# USBIface.net
KiCad netlist of a schematic drawn in Altium Designer
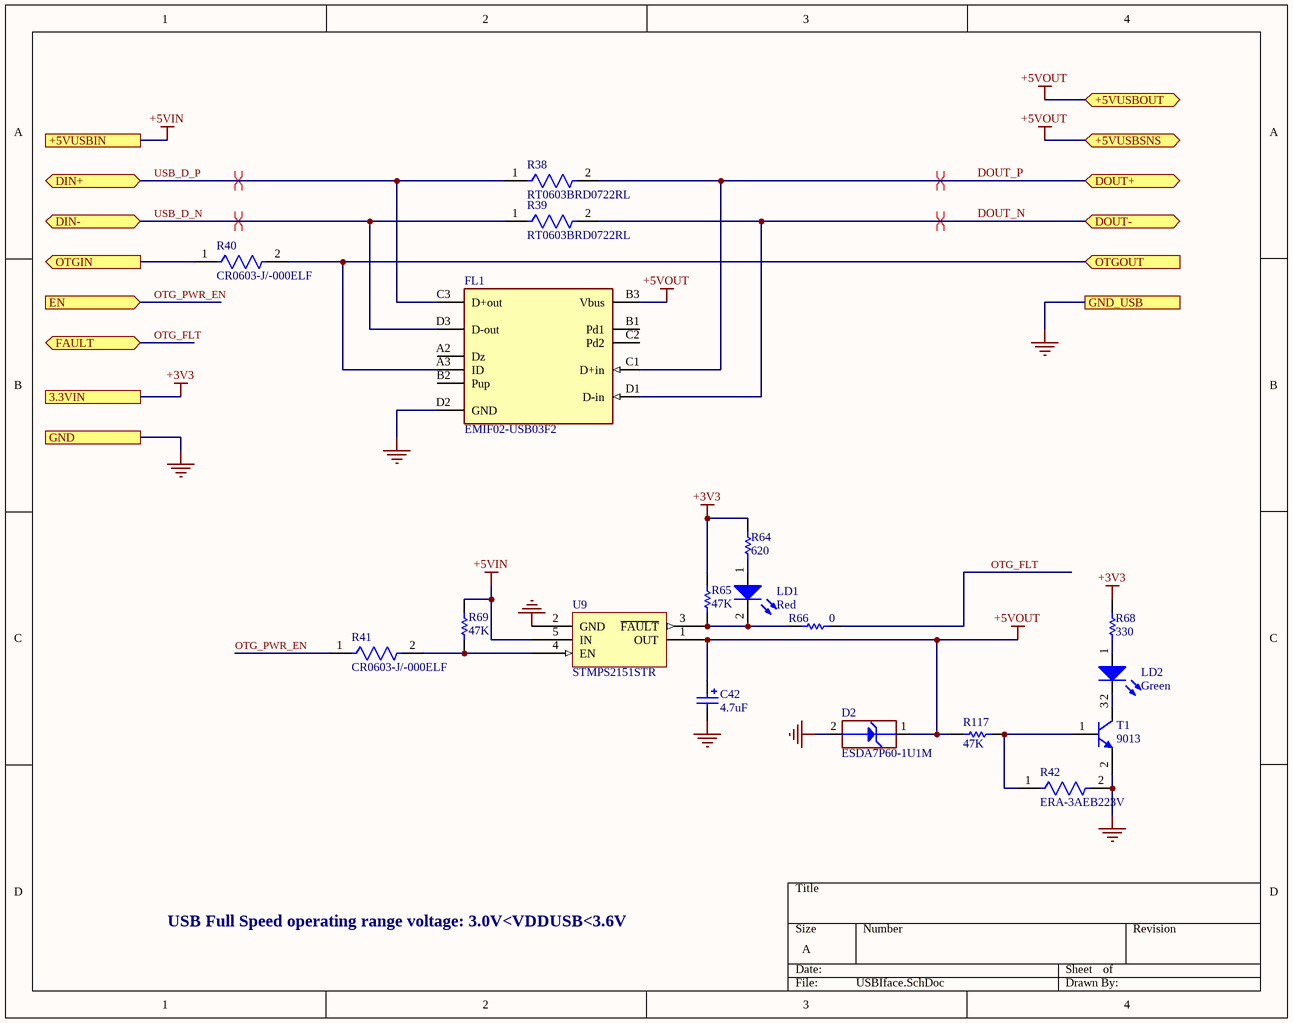
[diagram p0: USBIface.SchDoc]

(export (version "E")
  (design (tool "Eeschema 10.0.6"))
  (components
    (comp (ref "C42")
      (value "4.7uF")
      (footprint "TAN-A")
      (description "Polarized Capacitor (Radial)")
      (fields (field (name "PUBLISHER") "Altium Limited"))
      (libsource (lib "Miscellaneous Devices") (part "Cap Pol1"))
    )
    (comp (ref "D2")
      (value "ESDA7P60-1U1M")
      (footprint "DO_2SM_1R6X1_21")
      (description "High power transient voltage suppressor, 7V breakdown")
      (fields (field (name "INTERNAL_PART_NUMBER") "MCD-00251") (field (name "PROVIDED_BY") "STM"))
      (libsource (lib "MCD_PARTS_database") (part "ESDA7P60-1U1M"))
    )
    (comp (ref "FL1")
      (value "EMIF02-USB03F2")
      (footprint "FP-EMIF02-USB03F2-MFG")
      (description "FILTER RC(PI) 33 OHM/20PF SMD")
      (fields (field (name "TOLERANCE") "5%"))
      (libsource (lib "Altium Content Vault") (part "91055883b371ba38c36932eb47b762f"))
    )
    (comp (ref "LD1")
      (value "Red")
      (footprint "0603D")
      (description "Typical RED, GREEN, YELLOW, AMBER GaAs LED")
      (fields (field (name "PUBLISHER") "Altium Limited"))
      (libsource (lib "Miscellaneous Devices") (part "LED2"))
    )
    (comp (ref "LD2")
      (value "Green")
      (footprint "0603D")
      (description "Typical RED, GREEN, YELLOW, AMBER GaAs LED")
      (fields (field (name "PUBLISHER") "Altium Limited"))
      (libsource (lib "Miscellaneous Devices") (part "LED2"))
    )
    (comp (ref "R38")
      (value "RT0603BRD0722RL")
      (footprint "FP-RT0603-MFG")
      (description "RES SMD 22 OHM 0.1% 1/10W 0603")
      (fields
        (field (name "MANUFACTURER") "Yageo")
        (field (name "OCTOPART") "https://octopart.com/rt0603brd0722rl-yageo-1422899")
      )
      (libsource (lib "Altium Content Vault") (part "1029c3af85768c4190bb7ad29bc67b5"))
    )
    (comp (ref "R39")
      (value "RT0603BRD0722RL")
      (footprint "FP-RT0603-MFG")
      (description "RES SMD 22 OHM 0.1% 1/10W 0603")
      (fields
        (field (name "MANUFACTURER") "Yageo")
        (field (name "OCTOPART") "https://octopart.com/rt0603brd0722rl-yageo-1422899")
      )
      (libsource (lib "Altium Content Vault") (part "1029c3af85768c4190bb7ad29bc67b5"))
    )
    (comp (ref "R40")
      (value "CR0603-J/-000ELF")
      (footprint "FP-CR0603-MFG")
      (description "Thick Film Chip Resistors 0603 0Ω 0.1W 5%")
      (fields (field (name "TOLERANCE") "1%"))
      (libsource (lib "Altium Content Vault") (part "1029c3af85768c4190bb7ad29bc67b5"))
    )
    (comp (ref "R41")
      (value "CR0603-J/-000ELF")
      (footprint "FP-CR0603-MFG")
      (description "Thick Film Chip Resistors 0603 0Ω 0.1W 5%")
      (fields (field (name "TOLERANCE") "1%"))
      (libsource (lib "Altium Content Vault") (part "1029c3af85768c4190bb7ad29bc67b5"))
    )
    (comp (ref "R42")
      (value "ERA-3AEB223V")
      (footprint "FP-ERA3A-MFG")
      (description "RES SMD 22K OHM 0.1% 1/10W 0603")
      (fields (field (name "TOLERANCE") "0.1%"))
      (libsource (lib "Altium Content Vault") (part "1029c3af85768c4190bb7ad29bc67b5"))
    )
    (comp (ref "R64")
      (value "620")
      (footprint "0603R")
      (description "Resistor")
      (fields (field (name "PUBLISHER") "Altium Limited"))
      (libsource (lib "Miscellaneous Devices") (part "Res1"))
    )
    (comp (ref "R65")
      (value "47K")
      (footprint "0603R")
      (description "Resistor")
      (fields (field (name "PUBLISHER") "Altium Limited"))
      (libsource (lib "Miscellaneous Devices") (part "res1"))
    )
    (comp (ref "R66")
      (value "0")
      (footprint "0603R")
      (description "Resistor")
      (fields (field (name "PUBLISHER") "Altium Limited"))
      (libsource (lib "Miscellaneous Devices") (part "Res1"))
    )
    (comp (ref "R68")
      (value "330")
      (footprint "0603R")
      (description "Resistor")
      (fields (field (name "PUBLISHER") "Altium Limited"))
      (libsource (lib "Miscellaneous Devices") (part "res1"))
    )
    (comp (ref "R69")
      (value "47K")
      (footprint "0603R")
      (description "Resistor")
      (fields (field (name "PUBLISHER") "Altium Limited"))
      (libsource (lib "Miscellaneous Devices") (part "Res1"))
    )
    (comp (ref "R117")
      (value "47K")
      (footprint "0603R")
      (description "Resistor")
      (fields (field (name "PUBLISHER") "Altium Limited"))
      (libsource (lib "Miscellaneous Devices") (part "res1"))
    )
    (comp (ref "T1")
      (value "9013")
      (footprint "SOT-23")
      (description "NPN Bipolar Transistor")
      (fields (field (name "PUBLISHER") "Altium Limited"))
      (libsource (lib "MB1167") (part "NPN"))
    )
    (comp (ref "U9")
      (value "STMPS2151STR")
      (footprint "SOT23-5N")
      (libsource (lib "mb1045") (part "STMPS2141STR"))
    )
  )
  (nets
    (net (code "1") (name "+3V3") (class "Default")
      (node (ref "R64") (pin "2") (pinfunction "2_2") (pintype "passive"))
      (node (ref "R65") (pin "1") (pinfunction "1_1") (pintype "passive"))
      (node (ref "R68") (pin "2") (pinfunction "2_2") (pintype "passive"))
    )
    (net (code "2") (name "+5VIN") (class "Default")
      (node (ref "R69") (pin "2") (pinfunction "2_2") (pintype "passive"))
      (node (ref "U9") (pin "5") (pinfunction "IN_5") (pintype "passive"))
    )
    (net (code "3") (name "+5VOUT") (class "Default")
      (node (ref "C42") (pin "1") (pinfunction "1_1") (pintype "passive"))
      (node (ref "D2") (pin "1") (pinfunction "IO1_1") (pintype "passive"))
      (node (ref "FL1") (pin "B3") (pinfunction "Vbus_B3") (pintype "passive"))
      (node (ref "R117") (pin "1") (pinfunction "1_1") (pintype "passive"))
      (node (ref "U9") (pin "1") (pinfunction "OUT_1") (pintype "passive"))
    )
    (net (code "4") (name "/DOUT_N") (class "Default")
      (node (ref "FL1") (pin "D1") (pinfunction "D-in_D1") (pintype "input"))
      (node (ref "R39") (pin "2") (pinfunction "2_2") (pintype "passive"))
    )
    (net (code "5") (name "/DOUT_P") (class "Default")
      (node (ref "FL1") (pin "C1") (pinfunction "D+in_C1") (pintype "input"))
      (node (ref "R38") (pin "2") (pinfunction "2_2") (pintype "passive"))
    )
    (net (code "6") (name "/OTGIN") (class "Default")
      (node (ref "R40") (pin "1") (pinfunction "1_1") (pintype "passive"))
    )
    (net (code "7") (name "/OTGOUT") (class "Default")
      (node (ref "FL1") (pin "A3") (pinfunction "ID_A3") (pintype "passive"))
      (node (ref "R40") (pin "2") (pinfunction "2_2") (pintype "passive"))
    )
    (net (code "8") (name "/OTG_FLT") (class "Default")
      (node (ref "R66") (pin "1") (pinfunction "1_1") (pintype "passive"))
    )
    (net (code "9") (name "/OTG_PWR_EN") (class "Default")
      (node (ref "R41") (pin "1") (pinfunction "1_1") (pintype "passive"))
    )
    (net (code "10") (name "/USB_D_N") (class "Default")
      (node (ref "FL1") (pin "D3") (pinfunction "D-out_D3") (pintype "passive"))
      (node (ref "R39") (pin "1") (pinfunction "1_1") (pintype "passive"))
    )
    (net (code "11") (name "/USB_D_P") (class "Default")
      (node (ref "FL1") (pin "C3") (pinfunction "D+out_C3") (pintype "passive"))
      (node (ref "R38") (pin "1") (pinfunction "1_1") (pintype "passive"))
    )
    (net (code "12") (name "GND") (class "Default")
      (node (ref "C42") (pin "2") (pinfunction "2_2") (pintype "passive"))
      (node (ref "D2") (pin "2") (pinfunction "GND_2") (pintype "passive"))
      (node (ref "FL1") (pin "D2") (pinfunction "GND_D2") (pintype "power_in"))
      (node (ref "R42") (pin "2") (pinfunction "2_2") (pintype "passive"))
      (node (ref "T1") (pin "2") (pinfunction "E_2") (pintype "passive"))
      (node (ref "U9") (pin "2") (pinfunction "GND_2") (pintype "passive"))
    )
    (net (code "13") (name "Net-(LD1-A)") (class "Default")
      (node (ref "LD1") (pin "1") (pinfunction "A_1") (pintype "passive"))
      (node (ref "R64") (pin "1") (pinfunction "1_1") (pintype "passive"))
    )
    (net (code "14") (name "Net-(LD1-K)") (class "Default")
      (node (ref "LD1") (pin "2") (pinfunction "K_2") (pintype "passive"))
      (node (ref "R65") (pin "2") (pinfunction "2_2") (pintype "passive"))
      (node (ref "R66") (pin "2") (pinfunction "2_2") (pintype "passive"))
      (node (ref "U9") (pin "3") (pinfunction "~{FAULT}_3") (pintype "output"))
    )
    (net (code "15") (name "Net-(LD2-A)") (class "Default")
      (node (ref "LD2") (pin "1") (pinfunction "A_1") (pintype "passive"))
      (node (ref "R68") (pin "1") (pinfunction "1_1") (pintype "passive"))
    )
    (net (code "16") (name "Net-(LD2-K)") (class "Default")
      (node (ref "LD2") (pin "2") (pinfunction "K_2") (pintype "passive"))
      (node (ref "T1") (pin "3") (pinfunction "C_3") (pintype "passive"))
    )
    (net (code "17") (name "Net-(T1-B)") (class "Default")
      (node (ref "R117") (pin "2") (pinfunction "2_2") (pintype "passive"))
      (node (ref "R42") (pin "1") (pinfunction "1_1") (pintype "passive"))
      (node (ref "T1") (pin "1") (pinfunction "B_1") (pintype "passive"))
    )
    (net (code "18") (name "Net-(U9-EN)") (class "Default")
      (node (ref "R41") (pin "2") (pinfunction "2_2") (pintype "passive"))
      (node (ref "R69") (pin "1") (pinfunction "1_1") (pintype "passive"))
      (node (ref "U9") (pin "4") (pinfunction "EN_4") (pintype "input"))
    )
    (net (code "19") (name "unconnected-(FL1-Dz-PadA2)") (class "Default")
      (node (ref "FL1") (pin "A2") (pinfunction "Dz_A2") (pintype "passive"))
    )
    (net (code "20") (name "unconnected-(FL1-Pd1-PadB1)") (class "Default")
      (node (ref "FL1") (pin "B1") (pinfunction "Pd1_B1") (pintype "passive"))
    )
    (net (code "21") (name "unconnected-(FL1-Pd2-PadC2)") (class "Default")
      (node (ref "FL1") (pin "C2") (pinfunction "Pd2_C2") (pintype "passive"))
    )
    (net (code "22") (name "unconnected-(FL1-Pup-PadB2)") (class "Default")
      (node (ref "FL1") (pin "B2") (pinfunction "Pup_B2") (pintype "passive"))
    )
  )
)
